# DynoUSB_10.net
KiCad netlist of a schematic drawn in EAGLE
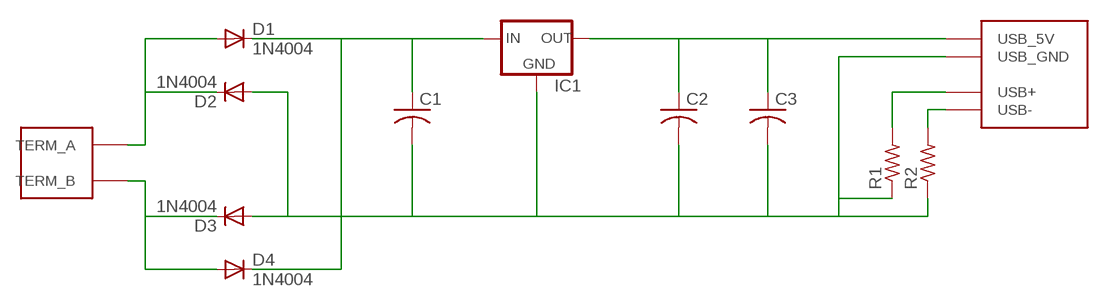
[diagram p0: schematic, sheet 1]

(export (version "E")
  (design (tool "Eeschema 10.0.6"))
  (components
    (comp (ref "C1")
      (value "C-USC1206")
      (footprint "eagle-import:C1206")
      (libsource (lib "eagle-import") (part "C-USC1206"))
    )
    (comp (ref "C2")
      (value "C-USC1206")
      (footprint "eagle-import:C1206")
      (libsource (lib "eagle-import") (part "C-USC1206"))
    )
    (comp (ref "C3")
      (value "C-USC3216")
      (footprint "eagle-import:C3216")
      (libsource (lib "eagle-import") (part "C-USC3216"))
    )
    (comp (ref "D1")
      (value "1N4004")
      (footprint "eagle-import:DO41-10")
      (libsource (lib "eagle-import") (part "1N4004"))
    )
    (comp (ref "D2")
      (value "1N4004")
      (footprint "eagle-import:DO41-10")
      (libsource (lib "eagle-import") (part "1N4004"))
    )
    (comp (ref "D3")
      (value "1N4004")
      (footprint "eagle-import:DO41-10")
      (libsource (lib "eagle-import") (part "1N4004"))
    )
    (comp (ref "D4")
      (value "1N4004")
      (footprint "eagle-import:DO41-10")
      (libsource (lib "eagle-import") (part "1N4004"))
    )
    (comp (ref "IC1")
      (value "78XXL")
      (footprint "eagle-import:78XXL")
      (libsource (lib "eagle-import") (part "78XXL"))
    )
    (comp (ref "R1")
      (value "R-US_M1206")
      (footprint "eagle-import:M1206")
      (libsource (lib "eagle-import") (part "R-US_M1206"))
    )
    (comp (ref "R2")
      (value "R-US_M1206")
      (footprint "eagle-import:M1206")
      (libsource (lib "eagle-import") (part "R-US_M1206"))
    )
    (comp (ref "U$1")
      (value "SPARKFUN_USB_A")
      (footprint "eagle-import:USB_4UCON_18666_318")
      (libsource (lib "eagle-import") (part "SPARKFUN_USB_A"))
    )
    (comp (ref "U$2")
      (value "SCREW_TERM_2")
      (footprint "eagle-import:SCREWTERMINAL-5MM-2")
      (libsource (lib "eagle-import") (part "SCREW_TERM_2"))
    )
  )
  (nets
    (net (code "1") (name "Net-(C1-Pad1)") (class "Default")
      (node (ref "C1") (pin "1") (pinfunction "1_1") (pintype "passive"))
      (node (ref "D1") (pin "C") (pinfunction "C_C") (pintype "passive"))
      (node (ref "D4") (pin "C") (pinfunction "C_C") (pintype "passive"))
      (node (ref "IC1") (pin "IN") (pinfunction "IN_IN") (pintype "input"))
    )
    (net (code "2") (name "Net-(C1-Pad2)") (class "Default")
      (node (ref "C1") (pin "2") (pinfunction "2_2") (pintype "passive"))
      (node (ref "C2") (pin "2") (pinfunction "2_2") (pintype "passive"))
      (node (ref "C3") (pin "2") (pinfunction "2_2") (pintype "passive"))
      (node (ref "D2") (pin "A") (pinfunction "A_A") (pintype "passive"))
      (node (ref "D3") (pin "A") (pinfunction "A_A") (pintype "passive"))
      (node (ref "IC1") (pin "GND") (pinfunction "GND_GND") (pintype "input"))
      (node (ref "R1") (pin "1") (pinfunction "1_1") (pintype "passive"))
      (node (ref "R2") (pin "1") (pinfunction "1_1") (pintype "passive"))
      (node (ref "U$1") (pin "USB_GND") (pinfunction "USB_GND_USB_GND") (pintype "bidirectional"))
    )
    (net (code "3") (name "Net-(C2-Pad1)") (class "Default")
      (node (ref "C2") (pin "1") (pinfunction "1_1") (pintype "passive"))
      (node (ref "C3") (pin "1") (pinfunction "1_1") (pintype "passive"))
      (node (ref "IC1") (pin "OUT") (pinfunction "OUT_OUT") (pintype "passive"))
      (node (ref "U$1") (pin "USB_5V") (pinfunction "USB_5V_USB_5V") (pintype "bidirectional"))
    )
    (net (code "4") (name "Net-(R1-Pad2)") (class "Default")
      (node (ref "R1") (pin "2") (pinfunction "2_2") (pintype "passive"))
      (node (ref "U$1") (pin "USB+") (pinfunction "USB+_USB+") (pintype "bidirectional"))
    )
    (net (code "5") (name "Net-(R2-Pad2)") (class "Default")
      (node (ref "R2") (pin "2") (pinfunction "2_2") (pintype "passive"))
      (node (ref "U$1") (pin "USB-") (pinfunction "USB-_USB-") (pintype "bidirectional"))
    )
    (net (code "6") (name "Net-(U$2-TERM_A)") (class "Default")
      (node (ref "D1") (pin "A") (pinfunction "A_A") (pintype "passive"))
      (node (ref "D2") (pin "C") (pinfunction "C_C") (pintype "passive"))
      (node (ref "U$2") (pin "1") (pinfunction "TERM_A_1") (pintype "bidirectional"))
    )
    (net (code "7") (name "Net-(U$2-TERM_B)") (class "Default")
      (node (ref "D3") (pin "C") (pinfunction "C_C") (pintype "passive"))
      (node (ref "D4") (pin "A") (pinfunction "A_A") (pintype "passive"))
      (node (ref "U$2") (pin "2") (pinfunction "TERM_B_2") (pintype "bidirectional"))
    )
  )
)
